# pulseox.net
KiCad netlist of a schematic drawn in Altium Designer
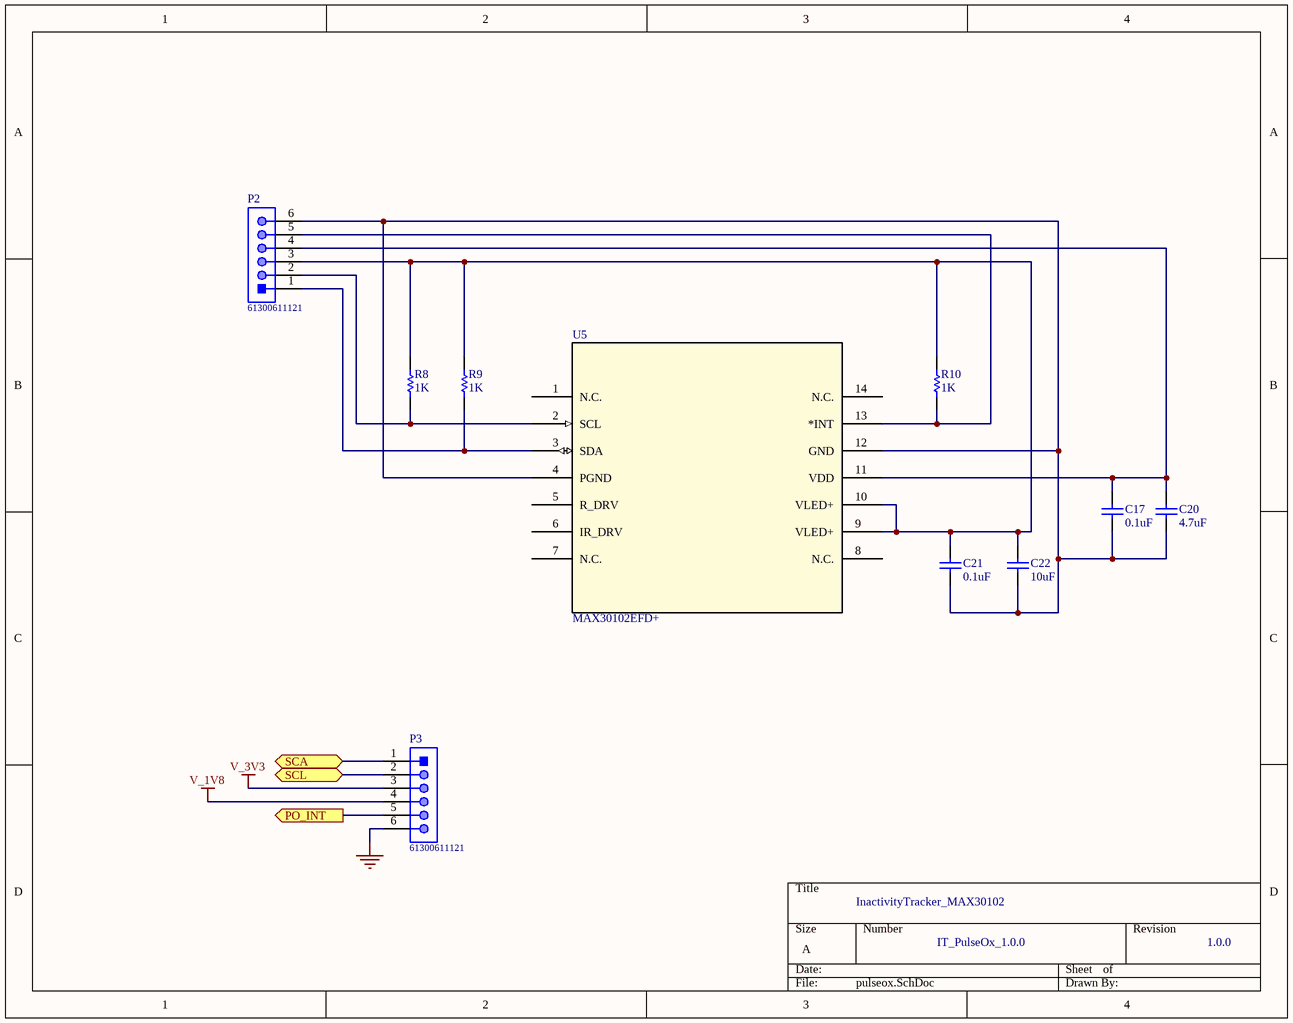
[diagram p0: pulseox.SchDoc]

(export (version "E")
  (design (tool "Eeschema 10.0.6"))
  (components
    (comp (ref "C17")
      (value "0.1uF")
      (footprint "CAPC1005X55X25ML05T10")
      (description "Chip Capacitor, 0.1 uF, +/- 10%, 16 V, -55 to 125 degC, 0402 (1005 Metric), RoHS, Tape and Reel")
      (fields (field (name "VOLTAGE") "16V") (field (name "TOLERANCE") "10%"))
      (libsource (lib "Altium Content Vault") (part "CAP-NP-2"))
    )
    (comp (ref "C20")
      (value "4.7uF")
      (footprint "CAPC1005X55X25NL05T10")
      (fields (field (name "PART NUMBER") "GRM155R60J475ME47D") (field (name "MANUFACTURER") "Murata"))
      (libsource (lib "Altium Content Vault") (part "CAP"))
    )
    (comp (ref "C21")
      (value "0.1uF")
      (footprint "CAPC1005X55X25ML05T10")
      (description "Chip Capacitor, 0.1 uF, +/- 10%, 16 V, -55 to 125 degC, 0402 (1005 Metric), RoHS, Tape and Reel")
      (fields (field (name "VOLTAGE") "16V") (field (name "TOLERANCE") "10%"))
      (libsource (lib "Altium Content Vault") (part "CAP-NP-2"))
    )
    (comp (ref "C22")
      (value "10uF")
      (footprint "CAPC1608X90X35NL10T15")
      (fields (field (name "PART NUMBER") "GRM188R60J106ME47D") (field (name "MANUFACTURER") "Murata"))
      (libsource (lib "Altium Content Vault") (part "CAP"))
    )
    (comp (ref "P2")
      (value "61300611121")
      (footprint "61300611121")
      (description "THT Vertical Pin Header WR-PHD, Pitch 2.54 mm, Single Row, 6 pins")
      (fields (field (name "MANUFACTURER") "Wurth Elektronik") (field (name "PUBLISHER") "WurthElektronik"))
      (libsource (lib "Altium Content Vault") (part "WE-CN-1P-M-R6"))
    )
    (comp (ref "P3")
      (value "61300611121")
      (footprint "61300611121")
      (description "THT Vertical Pin Header WR-PHD, Pitch 2.54 mm, Single Row, 6 pins")
      (fields (field (name "MANUFACTURER") "Wurth Elektronik") (field (name "PUBLISHER") "WurthElektronik"))
      (libsource (lib "") (part "WE-CN-1P-M-R6_1"))
    )
    (comp (ref "R8")
      (value "1K")
      (footprint "RESC1005X40X25NL05T05")
      (fields (field (name "MANUFACTURER") "Vishay Dale") (field (name "PART NUMBER") "CRCW04021K00FKED"))
      (libsource (lib "Altium Content Vault") (part "RES"))
    )
    (comp (ref "R9")
      (value "1K")
      (footprint "RESC1005X40X25NL05T05")
      (fields (field (name "MANUFACTURER") "Vishay Dale") (field (name "PART NUMBER") "CRCW04021K00FKED"))
      (libsource (lib "Altium Content Vault") (part "RES"))
    )
    (comp (ref "R10")
      (value "1K")
      (footprint "RESC1005X40X25NL05T05")
      (fields (field (name "MANUFACTURER") "Vishay Dale") (field (name "PART NUMBER") "CRCW04021K00FKED"))
      (libsource (lib "Altium Content Vault") (part "RES"))
    )
    (comp (ref "U5")
      (value "MAX30102EFD+")
      (footprint "21-0880B-L")
      (description "IC SENSOR OXIMETER/HEARTRATE")
      (fields (field (name "MANUFACTURER") "Maxim"))
      (libsource (lib "MaximIntegrated") (part "MAX30102EFD+"))
    )
  )
  (nets
    (net (code "1") (name "/PO_INT") (class "Default")
      (node (ref "P3") (pin "5") (pinfunction "5_5") (pintype "passive"))
    )
    (net (code "2") (name "/SCA") (class "Default")
      (node (ref "P3") (pin "1") (pinfunction "1_1") (pintype "passive"))
    )
    (net (code "3") (name "/SCL") (class "Default")
      (node (ref "P3") (pin "2") (pinfunction "2_2") (pintype "passive"))
    )
    (net (code "4") (name "GND") (class "Default")
      (node (ref "P3") (pin "6") (pinfunction "6_6") (pintype "passive"))
    )
    (net (code "5") (name "Net-(C21-Pad1)") (class "Default")
      (node (ref "C21") (pin "1") (pinfunction "1_1") (pintype "passive"))
      (node (ref "C22") (pin "1") (pinfunction "1_1") (pintype "passive"))
      (node (ref "P2") (pin "3") (pinfunction "3_3") (pintype "passive"))
      (node (ref "R10") (pin "1") (pinfunction "1_1") (pintype "passive"))
      (node (ref "R8") (pin "2") (pinfunction "2_2") (pintype "passive"))
      (node (ref "R9") (pin "2") (pinfunction "2_2") (pintype "passive"))
      (node (ref "U5") (pin "10") (pinfunction "VLED+_10") (pintype "passive"))
      (node (ref "U5") (pin "9") (pinfunction "VLED+_9") (pintype "passive"))
    )
    (net (code "6") (name "Net-(U5-*INT)") (class "Default")
      (node (ref "P2") (pin "5") (pinfunction "5_5") (pintype "passive"))
      (node (ref "R10") (pin "2") (pinfunction "2_2") (pintype "passive"))
      (node (ref "U5") (pin "13") (pinfunction "*INT_13") (pintype "passive"))
    )
    (net (code "7") (name "Net-(U5-GND)") (class "Default")
      (node (ref "C17") (pin "2") (pinfunction "2_2") (pintype "passive"))
      (node (ref "C20") (pin "2") (pinfunction "2_2") (pintype "passive"))
      (node (ref "C21") (pin "2") (pinfunction "2_2") (pintype "passive"))
      (node (ref "C22") (pin "2") (pinfunction "2_2") (pintype "passive"))
      (node (ref "P2") (pin "6") (pinfunction "6_6") (pintype "passive"))
      (node (ref "U5") (pin "12") (pinfunction "GND_12") (pintype "power_in"))
      (node (ref "U5") (pin "4") (pinfunction "PGND_4") (pintype "power_in"))
    )
    (net (code "8") (name "Net-(U5-SCL)") (class "Default")
      (node (ref "P2") (pin "2") (pinfunction "2_2") (pintype "passive"))
      (node (ref "R8") (pin "1") (pinfunction "1_1") (pintype "passive"))
      (node (ref "U5") (pin "2") (pinfunction "SCL_2") (pintype "input"))
    )
    (net (code "9") (name "Net-(U5-SDA)") (class "Default")
      (node (ref "P2") (pin "1") (pinfunction "1_1") (pintype "passive"))
      (node (ref "R9") (pin "1") (pinfunction "1_1") (pintype "passive"))
      (node (ref "U5") (pin "3") (pinfunction "SDA_3") (pintype "bidirectional"))
    )
    (net (code "10") (name "Net-(U5-VDD)") (class "Default")
      (node (ref "C17") (pin "1") (pinfunction "1_1") (pintype "passive"))
      (node (ref "C20") (pin "1") (pinfunction "1_1") (pintype "passive"))
      (node (ref "P2") (pin "4") (pinfunction "4_4") (pintype "passive"))
      (node (ref "U5") (pin "11") (pinfunction "VDD_11") (pintype "power_in"))
    )
    (net (code "11") (name "V_1V8") (class "Default")
      (node (ref "P3") (pin "4") (pinfunction "4_4") (pintype "passive"))
    )
    (net (code "12") (name "V_3V3") (class "Default")
      (node (ref "P3") (pin "3") (pinfunction "3_3") (pintype "passive"))
    )
    (net (code "13") (name "unconnected-(U5-IR_DRV-Pad6)") (class "Default")
      (node (ref "U5") (pin "6") (pinfunction "IR_DRV_6") (pintype "passive"))
    )
    (net (code "14") (name "unconnected-(U5-N.C.-Pad1)") (class "Default")
      (node (ref "U5") (pin "1") (pinfunction "N.C._1") (pintype "passive"))
    )
    (net (code "15") (name "unconnected-(U5-N.C.-Pad7)") (class "Default")
      (node (ref "U5") (pin "7") (pinfunction "N.C._7") (pintype "passive"))
    )
    (net (code "16") (name "unconnected-(U5-N.C.-Pad8)") (class "Default")
      (node (ref "U5") (pin "8") (pinfunction "N.C._8") (pintype "passive"))
    )
    (net (code "17") (name "unconnected-(U5-N.C.-Pad14)") (class "Default")
      (node (ref "U5") (pin "14") (pinfunction "N.C._14") (pintype "passive"))
    )
    (net (code "18") (name "unconnected-(U5-R_DRV-Pad5)") (class "Default")
      (node (ref "U5") (pin "5") (pinfunction "R_DRV_5") (pintype "passive"))
    )
  )
)
